# DC_Sensor_ESP8266_ADC_NC_08.net
KiCad netlist of a schematic drawn in EAGLE
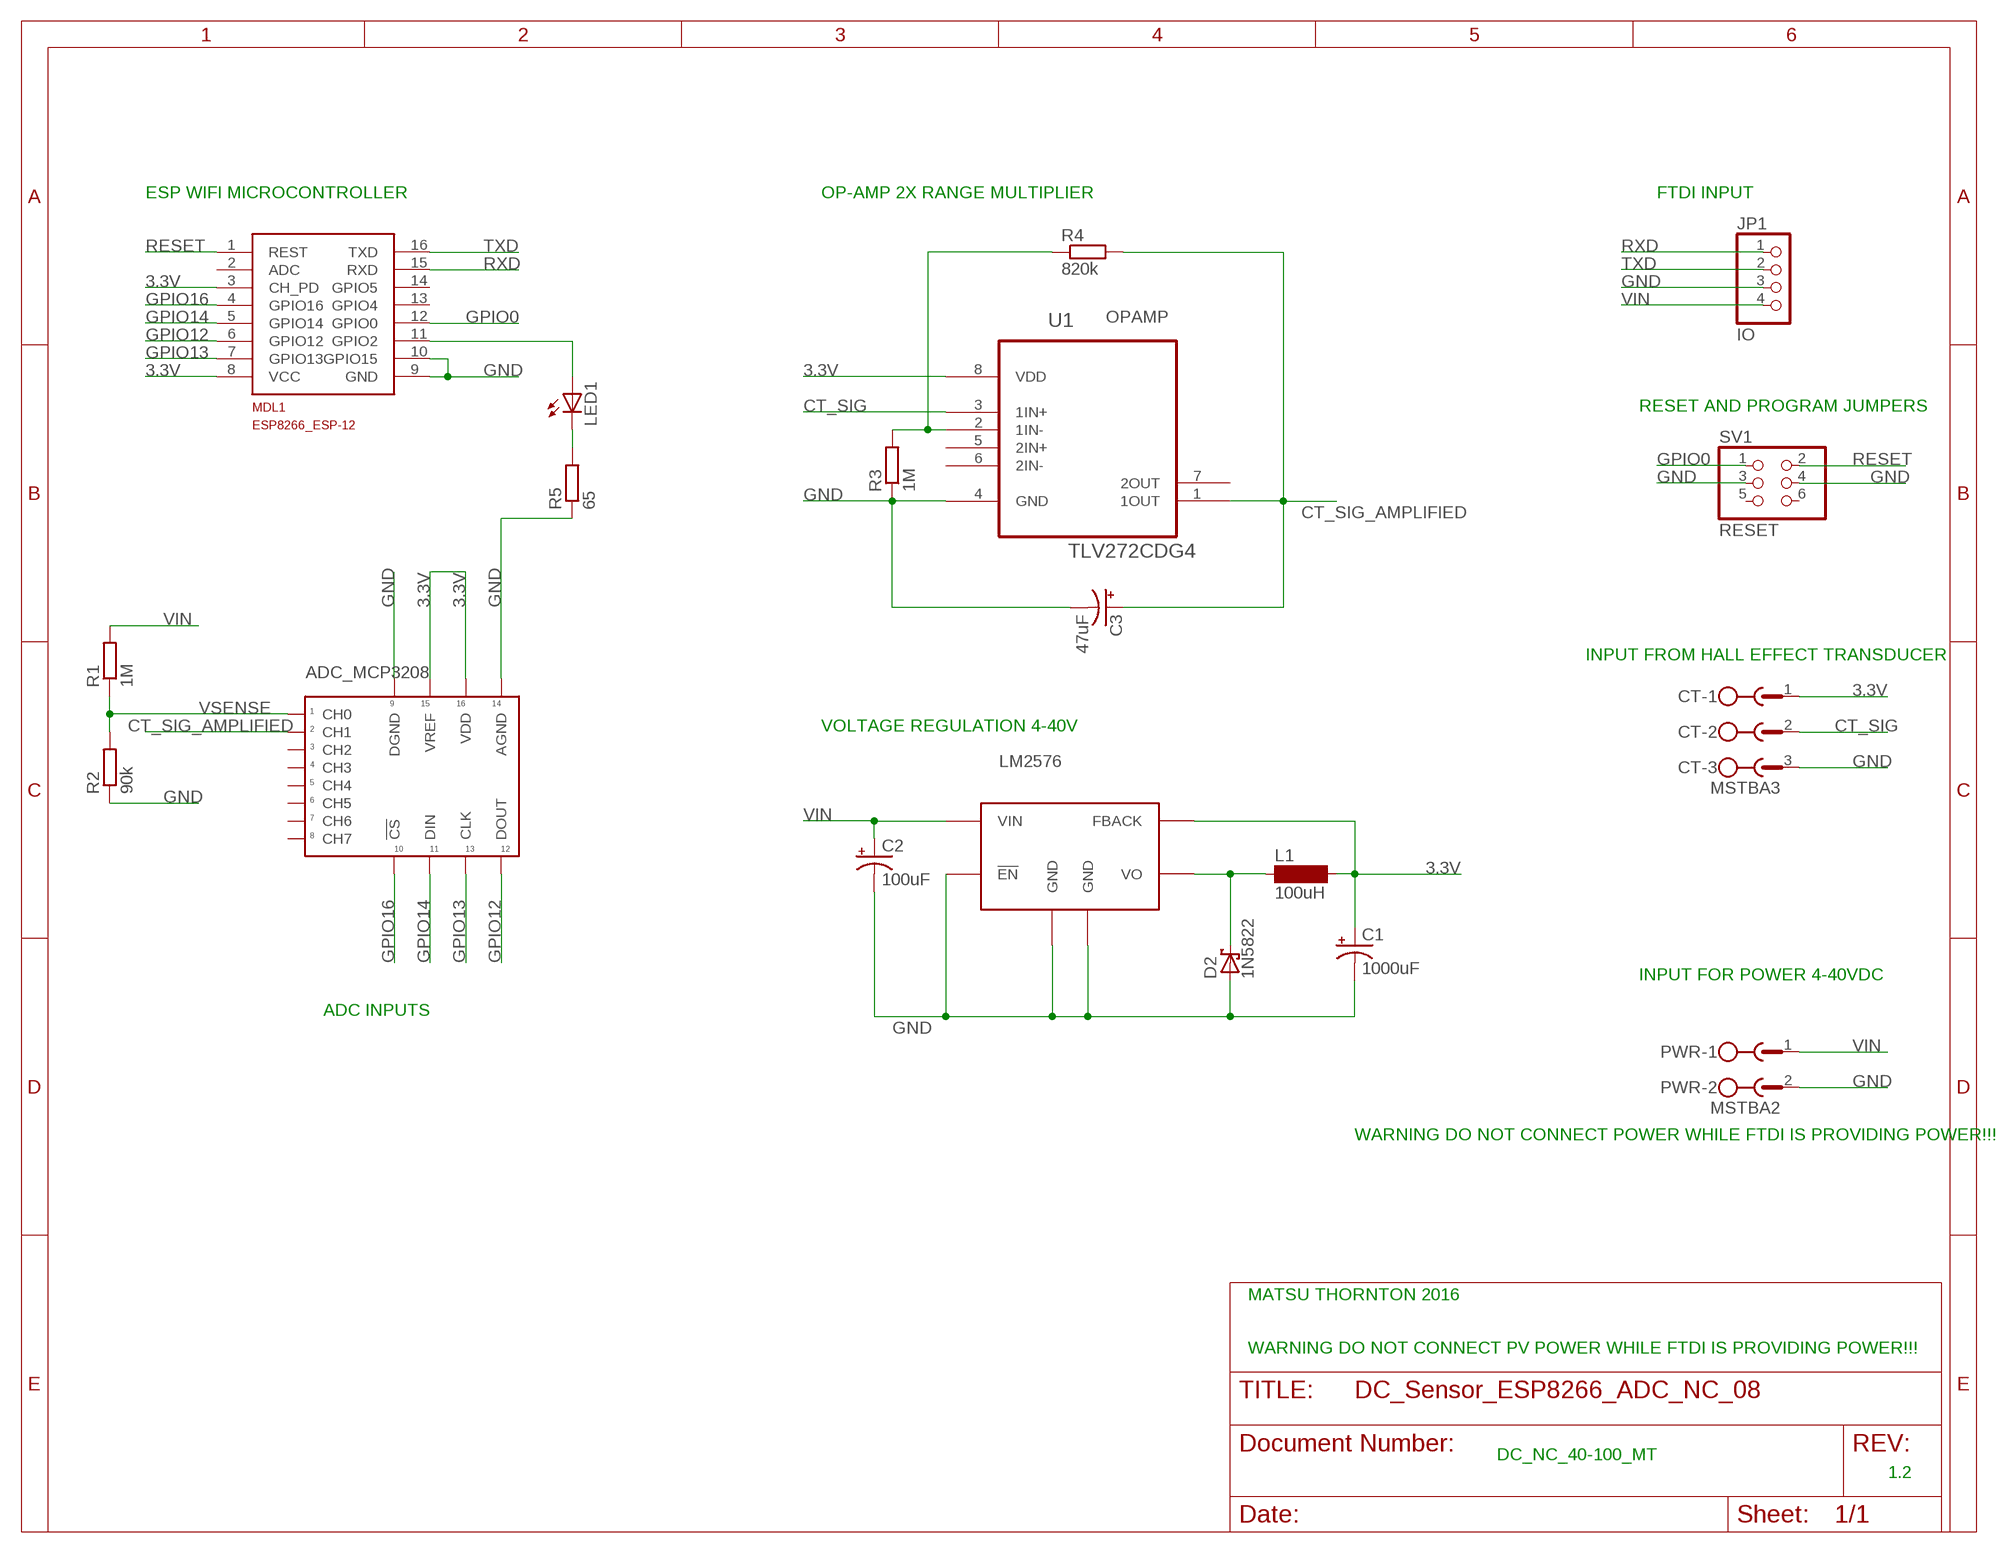
[diagram p0: schematic, sheet 1]

(export (version "E")
  (design (tool "Eeschema 10.0.6"))
  (components
    (comp (ref "ADC_MCP3208")
      (value "21298ESMD")
      (footprint "eagle-import:PDIP16")
      (libsource (lib "eagle-import") (part "21298ESMD"))
    )
    (comp (ref "C1")
      (value "1000uF")
      (footprint "eagle-import:PANASONIC_F")
      (libsource (lib "eagle-import") (part "CPOL-USF"))
    )
    (comp (ref "C2")
      (value "100uF")
      (footprint "eagle-import:PANASONIC_F")
      (libsource (lib "eagle-import") (part "CPOL-USF"))
    )
    (comp (ref "C3")
      (value "47uF")
      (footprint "eagle-import:PANASONIC_C")
      (libsource (lib "eagle-import") (part "CPOL-USC"))
    )
    (comp (ref "CT")
      (value "MSTBA3")
      (footprint "eagle-import:MSTBA3")
      (fields (field (name "MF") "FARNELL") (field (name "MPN") "1757255"))
      (libsource (lib "eagle-import") (part "MSTBA3"))
    )
    (comp (ref "D2")
      (value "1N5822")
      (footprint "eagle-import:C4111-15")
      (libsource (lib "eagle-import") (part "SCHOTTKY-DIODEC4111-15"))
    )
    (comp (ref "JP1")
      (value "IO")
      (footprint "eagle-import:1X04")
      (libsource (lib "eagle-import") (part "PINHD-1X4"))
    )
    (comp (ref "L1")
      (value "100uH")
      (footprint "eagle-import:BS11")
      (libsource (lib "eagle-import") (part "BS11"))
    )
    (comp (ref "LED1")
      (value "LEDCHIP-LED0603")
      (footprint "eagle-import:CHIP-LED0603")
      (libsource (lib "eagle-import") (part "LEDCHIP-LED0603"))
    )
    (comp (ref "LM2576")
      (value "LM2576S")
      (footprint "eagle-import:TO263-5")
      (libsource (lib "eagle-import") (part "LM2576S"))
    )
    (comp (ref "MDL1")
      (value "ESP8266-12GPIO04/05_CORRECTED")
      (footprint "eagle-import:ESP8266-ESP12")
      (libsource (lib "eagle-import") (part "ESP8266-12GPIO04/05_CORRECTED"))
    )
    (comp (ref "PWR")
      (value "MSTBA2")
      (footprint "eagle-import:MSTBA2")
      (fields (field (name "MF") "FARNELL") (field (name "MPN") "1757242"))
      (libsource (lib "eagle-import") (part "MSTBA2"))
    )
    (comp (ref "R1")
      (value "1M")
      (footprint "eagle-import:R0805")
      (libsource (lib "eagle-import") (part "R-EU_R0805"))
    )
    (comp (ref "R2")
      (value "90k")
      (footprint "eagle-import:R0805")
      (libsource (lib "eagle-import") (part "R-EU_R0805"))
    )
    (comp (ref "R3")
      (value "1M")
      (footprint "eagle-import:R0805")
      (libsource (lib "eagle-import") (part "R-EU_R0805"))
    )
    (comp (ref "R4")
      (value "820k")
      (footprint "eagle-import:R0805")
      (libsource (lib "eagle-import") (part "R-EU_R0805"))
    )
    (comp (ref "R5")
      (value "65")
      (footprint "eagle-import:R0805")
      (libsource (lib "eagle-import") (part "R-EU_R0805"))
    )
    (comp (ref "SV1")
      (value "RESET")
      (footprint "eagle-import:2X03")
      (libsource (lib "eagle-import") (part "PINHD-2X3"))
    )
    (comp (ref "U1")
      (value "TLV272CDG4")
      (footprint "eagle-import:SOIC127P600X175-8N")
      (fields (field (name "TYPE") "OPAMP"))
      (libsource (lib "eagle-import") (part "TLV272CDG4"))
    )
  )
  (nets
    (net (code "1") (name "/3.3V") (class "Default")
      (node (ref "ADC_MCP3208") (pin "P$15") (pinfunction "VREF_P$15") (pintype "bidirectional"))
      (node (ref "ADC_MCP3208") (pin "P$16") (pinfunction "VDD_P$16") (pintype "bidirectional"))
      (node (ref "C1") (pin "+") (pinfunction "+_+") (pintype "passive"))
      (node (ref "CT") (pin "1") (pinfunction "1_1") (pintype "passive"))
      (node (ref "L1") (pin "2") (pinfunction "2_2") (pintype "passive"))
      (node (ref "LM2576") (pin "4") (pinfunction "FBACK_4") (pintype "bidirectional"))
      (node (ref "MDL1") (pin "3") (pinfunction "CH_PD_3") (pintype "bidirectional"))
      (node (ref "MDL1") (pin "8") (pinfunction "VCC_8") (pintype "bidirectional"))
      (node (ref "U1") (pin "8") (pinfunction "VDD_8") (pintype "power_in"))
    )
    (net (code "2") (name "/CT_SIG") (class "Default")
      (node (ref "CT") (pin "2") (pinfunction "1_2") (pintype "passive"))
      (node (ref "U1") (pin "3") (pinfunction "1IN+_3") (pintype "input"))
    )
    (net (code "3") (name "/CT_SIG_AMPLIFIED") (class "Default")
      (node (ref "ADC_MCP3208") (pin "P$2") (pinfunction "CH1_P$2") (pintype "bidirectional"))
      (node (ref "C3") (pin "+") (pinfunction "+_+") (pintype "passive"))
      (node (ref "R4") (pin "2") (pinfunction "2_2") (pintype "passive"))
      (node (ref "U1") (pin "1") (pinfunction "1OUT_1") (pintype "output"))
    )
    (net (code "4") (name "/GND") (class "Default")
      (node (ref "ADC_MCP3208") (pin "P$14") (pinfunction "AGND_P$14") (pintype "bidirectional"))
      (node (ref "ADC_MCP3208") (pin "P$9") (pinfunction "DGND_P$9") (pintype "bidirectional"))
      (node (ref "C1") (pin "-") (pinfunction "-_-") (pintype "passive"))
      (node (ref "C2") (pin "-") (pinfunction "-_-") (pintype "passive"))
      (node (ref "C3") (pin "-") (pinfunction "-_-") (pintype "passive"))
      (node (ref "CT") (pin "3") (pinfunction "1_3") (pintype "passive"))
      (node (ref "D2") (pin "A") (pinfunction "A_A") (pintype "passive"))
      (node (ref "JP1") (pin "3") (pinfunction "3_3") (pintype "passive"))
      (node (ref "LM2576") (pin "3") (pinfunction "GND_3") (pintype "bidirectional"))
      (node (ref "LM2576") (pin "5") (pinfunction "~{EN}_5") (pintype "bidirectional"))
      (node (ref "LM2576") (pin "TAB") (pinfunction "GND_TAB") (pintype "bidirectional"))
      (node (ref "MDL1") (pin "10") (pinfunction "GPIO15_10") (pintype "bidirectional"))
      (node (ref "MDL1") (pin "9") (pinfunction "GND_9") (pintype "bidirectional"))
      (node (ref "PWR") (pin "2") (pinfunction "1_2") (pintype "passive"))
      (node (ref "R2") (pin "1") (pinfunction "1_1") (pintype "passive"))
      (node (ref "R3") (pin "1") (pinfunction "1_1") (pintype "passive"))
      (node (ref "R5") (pin "1") (pinfunction "1_1") (pintype "passive"))
      (node (ref "SV1") (pin "3") (pinfunction "3_3") (pintype "passive"))
      (node (ref "SV1") (pin "4") (pinfunction "4_4") (pintype "passive"))
      (node (ref "U1") (pin "4") (pinfunction "GND_4") (pintype "passive"))
    )
    (net (code "5") (name "/GPIO0") (class "Default")
      (node (ref "MDL1") (pin "12") (pinfunction "GPIO0_12") (pintype "bidirectional"))
      (node (ref "SV1") (pin "1") (pinfunction "1_1") (pintype "passive"))
    )
    (net (code "6") (name "/GPIO12") (class "Default")
      (node (ref "ADC_MCP3208") (pin "P$12") (pinfunction "DOUT_P$12") (pintype "bidirectional"))
      (node (ref "MDL1") (pin "6") (pinfunction "GPIO12_6") (pintype "bidirectional"))
    )
    (net (code "7") (name "/GPIO13") (class "Default")
      (node (ref "ADC_MCP3208") (pin "P$13") (pinfunction "CLK_P$13") (pintype "bidirectional"))
      (node (ref "MDL1") (pin "7") (pinfunction "GPIO13_7") (pintype "bidirectional"))
    )
    (net (code "8") (name "/GPIO14") (class "Default")
      (node (ref "ADC_MCP3208") (pin "P$11") (pinfunction "DIN_P$11") (pintype "bidirectional"))
      (node (ref "MDL1") (pin "5") (pinfunction "GPIO14_5") (pintype "bidirectional"))
    )
    (net (code "9") (name "/GPIO16") (class "Default")
      (node (ref "ADC_MCP3208") (pin "P$10") (pinfunction "~{CS}_P$10") (pintype "bidirectional"))
      (node (ref "MDL1") (pin "4") (pinfunction "GPIO16_4") (pintype "bidirectional"))
    )
    (net (code "10") (name "/RESET") (class "Default")
      (node (ref "MDL1") (pin "1") (pinfunction "REST_1") (pintype "bidirectional"))
      (node (ref "SV1") (pin "2") (pinfunction "2_2") (pintype "passive"))
    )
    (net (code "11") (name "/RXD") (class "Default")
      (node (ref "JP1") (pin "1") (pinfunction "1_1") (pintype "passive"))
      (node (ref "MDL1") (pin "15") (pinfunction "RXD_15") (pintype "bidirectional"))
    )
    (net (code "12") (name "/TXD") (class "Default")
      (node (ref "JP1") (pin "2") (pinfunction "2_2") (pintype "passive"))
      (node (ref "MDL1") (pin "16") (pinfunction "TXD_16") (pintype "bidirectional"))
    )
    (net (code "13") (name "/VIN") (class "Default")
      (node (ref "C2") (pin "+") (pinfunction "+_+") (pintype "passive"))
      (node (ref "JP1") (pin "4") (pinfunction "4_4") (pintype "passive"))
      (node (ref "LM2576") (pin "1") (pinfunction "VIN_1") (pintype "bidirectional"))
      (node (ref "PWR") (pin "1") (pinfunction "1_1") (pintype "passive"))
      (node (ref "R1") (pin "2") (pinfunction "2_2") (pintype "passive"))
    )
    (net (code "14") (name "/VSENSE") (class "Default")
      (node (ref "ADC_MCP3208") (pin "P$1") (pinfunction "CH0_P$1") (pintype "bidirectional"))
      (node (ref "R1") (pin "1") (pinfunction "1_1") (pintype "passive"))
      (node (ref "R2") (pin "2") (pinfunction "2_2") (pintype "passive"))
    )
    (net (code "15") (name "Net-(LED1-PadC)") (class "Default")
      (node (ref "LED1") (pin "C") (pinfunction "C_C") (pintype "passive"))
      (node (ref "R5") (pin "2") (pinfunction "2_2") (pintype "passive"))
    )
    (net (code "16") (name "Net-(LM2576-VO)") (class "Default")
      (node (ref "D2") (pin "C") (pinfunction "C_C") (pintype "passive"))
      (node (ref "L1") (pin "1") (pinfunction "1_1") (pintype "passive"))
      (node (ref "LM2576") (pin "2") (pinfunction "VO_2") (pintype "bidirectional"))
    )
    (net (code "17") (name "Net-(MDL1-GPIO2)") (class "Default")
      (node (ref "LED1") (pin "A") (pinfunction "A_A") (pintype "passive"))
      (node (ref "MDL1") (pin "11") (pinfunction "GPIO2_11") (pintype "bidirectional"))
    )
    (net (code "18") (name "Net-(U1-1IN-)") (class "Default")
      (node (ref "R3") (pin "2") (pinfunction "2_2") (pintype "passive"))
      (node (ref "R4") (pin "1") (pinfunction "1_1") (pintype "passive"))
      (node (ref "U1") (pin "2") (pinfunction "1IN-_2") (pintype "input"))
    )
    (net (code "19") (name "unconnected-(ADC_MCP3208-CH2-PadP$3)") (class "Default")
      (node (ref "ADC_MCP3208") (pin "P$3") (pinfunction "CH2_P$3") (pintype "bidirectional"))
    )
    (net (code "20") (name "unconnected-(ADC_MCP3208-CH3-PadP$4)") (class "Default")
      (node (ref "ADC_MCP3208") (pin "P$4") (pinfunction "CH3_P$4") (pintype "bidirectional"))
    )
    (net (code "21") (name "unconnected-(ADC_MCP3208-CH4-PadP$5)") (class "Default")
      (node (ref "ADC_MCP3208") (pin "P$5") (pinfunction "CH4_P$5") (pintype "bidirectional"))
    )
    (net (code "22") (name "unconnected-(ADC_MCP3208-CH5-PadP$6)") (class "Default")
      (node (ref "ADC_MCP3208") (pin "P$6") (pinfunction "CH5_P$6") (pintype "bidirectional"))
    )
    (net (code "23") (name "unconnected-(ADC_MCP3208-CH6-PadP$7)") (class "Default")
      (node (ref "ADC_MCP3208") (pin "P$7") (pinfunction "CH6_P$7") (pintype "bidirectional"))
    )
    (net (code "24") (name "unconnected-(ADC_MCP3208-CH7-PadP$8)") (class "Default")
      (node (ref "ADC_MCP3208") (pin "P$8") (pinfunction "CH7_P$8") (pintype "bidirectional"))
    )
    (net (code "25") (name "unconnected-(MDL1-ADC-Pad2)") (class "Default")
      (node (ref "MDL1") (pin "2") (pinfunction "ADC_2") (pintype "bidirectional"))
    )
    (net (code "26") (name "unconnected-(MDL1-GPIO4-Pad13)") (class "Default")
      (node (ref "MDL1") (pin "13") (pinfunction "GPIO4_13") (pintype "bidirectional"))
    )
    (net (code "27") (name "unconnected-(MDL1-GPIO5-Pad14)") (class "Default")
      (node (ref "MDL1") (pin "14") (pinfunction "GPIO5_14") (pintype "bidirectional"))
    )
    (net (code "28") (name "unconnected-(SV1-Pad5)") (class "Default")
      (node (ref "SV1") (pin "5") (pinfunction "5_5") (pintype "passive"))
    )
    (net (code "29") (name "unconnected-(SV1-Pad6)") (class "Default")
      (node (ref "SV1") (pin "6") (pinfunction "6_6") (pintype "passive"))
    )
    (net (code "30") (name "unconnected-(U1-2IN+-Pad5)") (class "Default")
      (node (ref "U1") (pin "5") (pinfunction "2IN+_5") (pintype "input"))
    )
    (net (code "31") (name "unconnected-(U1-2IN--Pad6)") (class "Default")
      (node (ref "U1") (pin "6") (pinfunction "2IN-_6") (pintype "input"))
    )
    (net (code "32") (name "unconnected-(U1-2OUT-Pad7)") (class "Default")
      (node (ref "U1") (pin "7") (pinfunction "2OUT_7") (pintype "output"))
    )
  )
)
